# powerboard.net
KiCad netlist of a schematic drawn in EAGLE
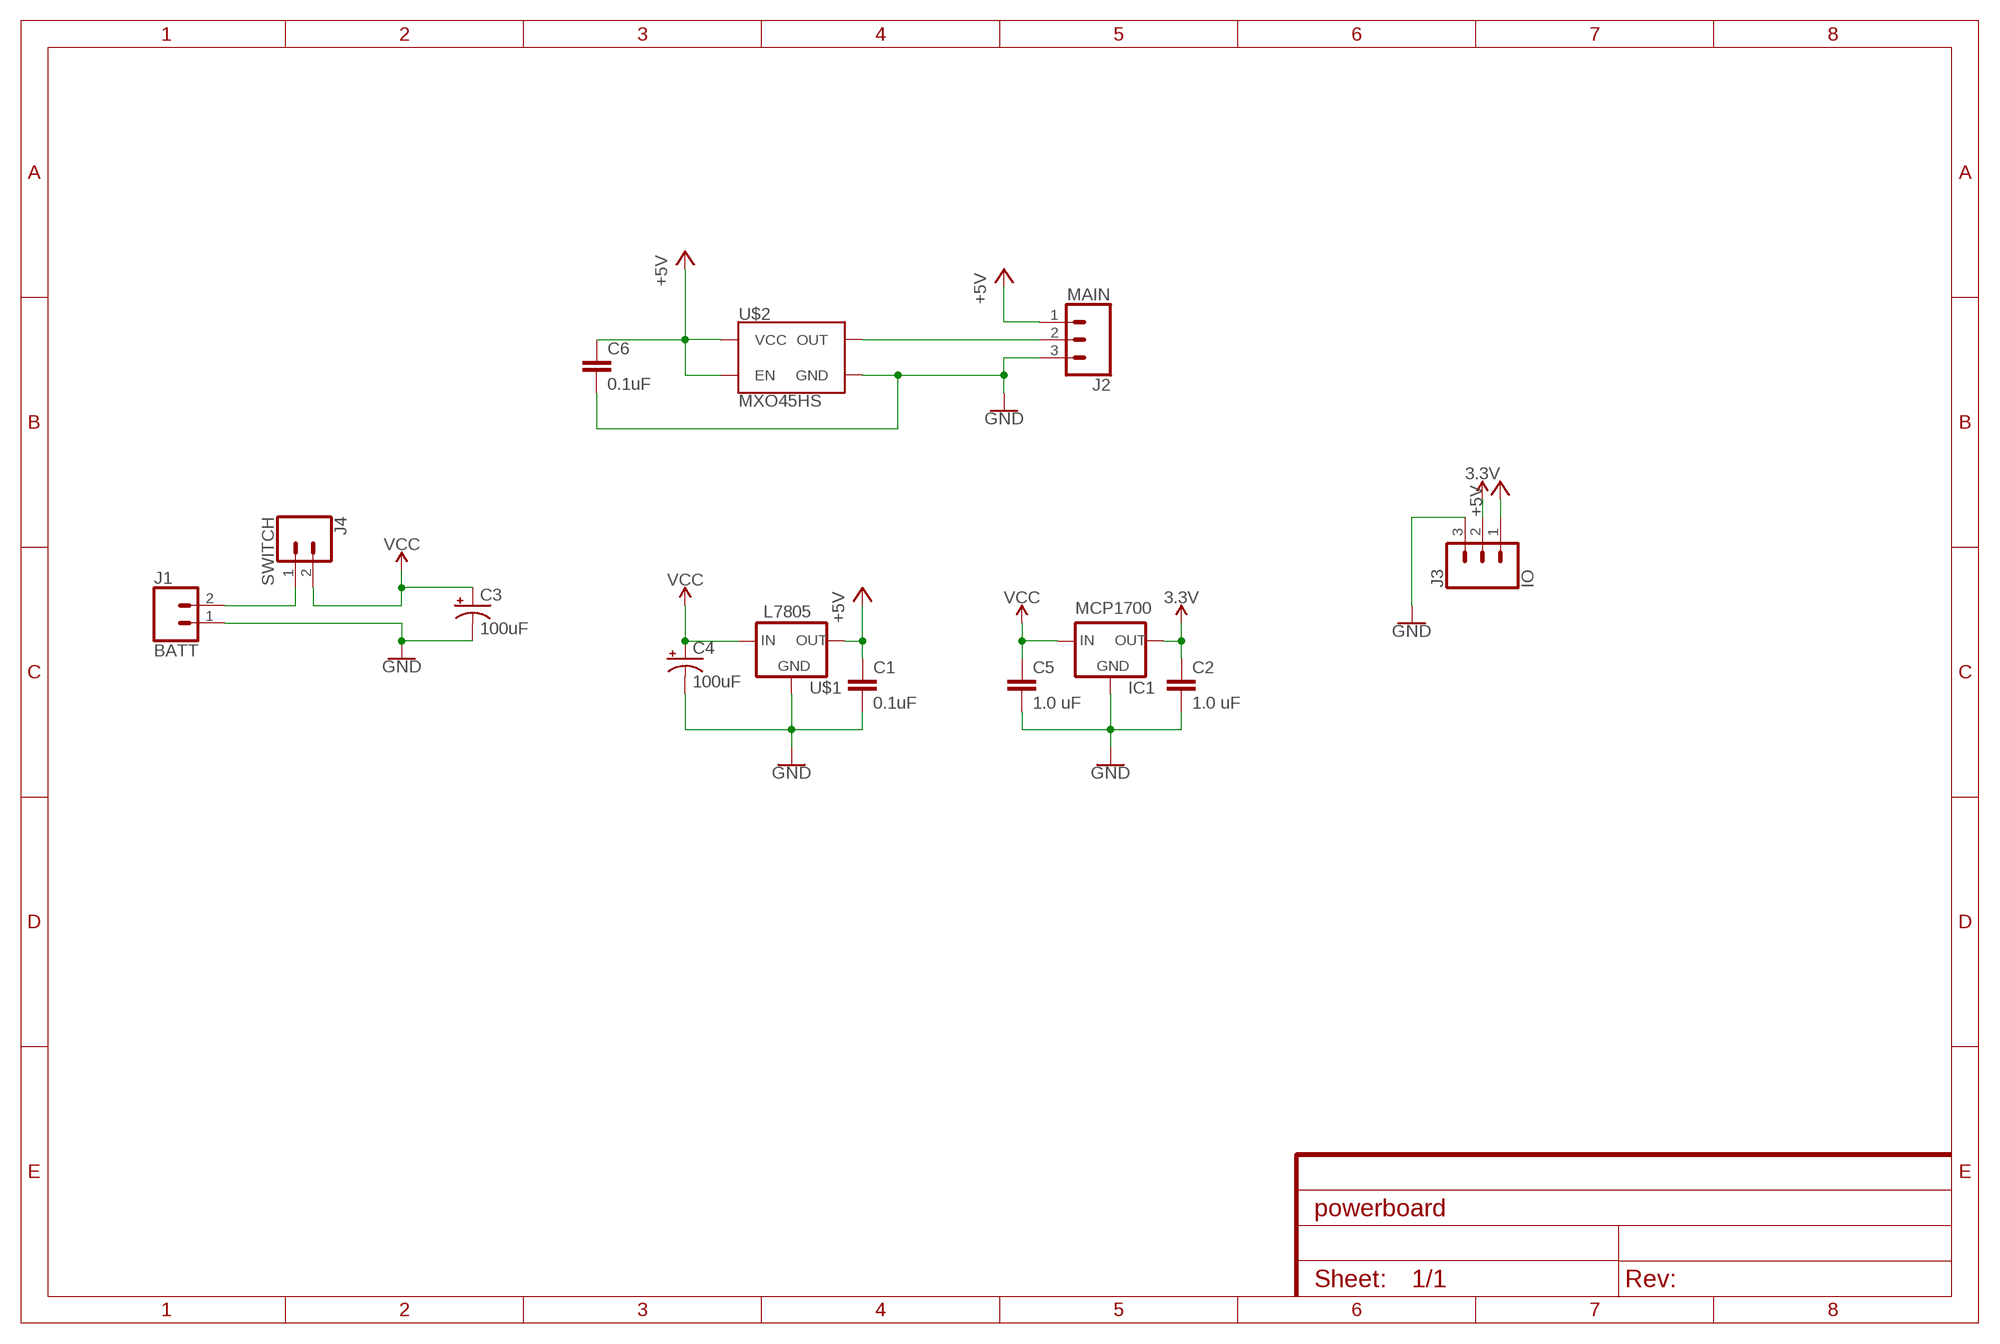
[diagram p0: schematic, sheet 1]

(export (version "E")
  (design (tool "Eeschema 10.0.6"))
  (components
    (comp (ref "C1")
      (value "0.1uF")
      (footprint "eagle-import:C2.5-3")
      (libsource (lib "eagle-import") (part "C2,5-3"))
    )
    (comp (ref "C2")
      (value "1.0 uF")
      (footprint "eagle-import:C2.5-3")
      (libsource (lib "eagle-import") (part "C2,5-3"))
    )
    (comp (ref "C3")
      (value "100uF")
      (footprint "eagle-import:CPOL-RADIAL-2.5MM-6.5MM")
      (libsource (lib "eagle-import") (part "100UF-POLAR-RADIAL-2.5MM-25V-20%"))
    )
    (comp (ref "C4")
      (value "100uF")
      (footprint "eagle-import:CPOL-RADIAL-2.5MM-6.5MM")
      (libsource (lib "eagle-import") (part "100UF-POLAR-RADIAL-2.5MM-25V-20%"))
    )
    (comp (ref "C5")
      (value "1.0 uF")
      (footprint "eagle-import:C2.5-3")
      (libsource (lib "eagle-import") (part "C2,5-3"))
    )
    (comp (ref "C6")
      (value "0.1uF")
      (footprint "eagle-import:C2.5-3")
      (libsource (lib "eagle-import") (part "C2,5-3"))
    )
    (comp (ref "IC1")
      (value "MCP1700")
      (footprint "eagle-import:TO-92-AMMO")
      (libsource (lib "eagle-import") (part "MCP1700"))
    )
    (comp (ref "J1")
      (value "BATT")
      (footprint "eagle-import:SCREWTERMINAL-5MM-2")
      (libsource (lib "eagle-import") (part "CONN_025MM"))
    )
    (comp (ref "J2")
      (value "MAIN")
      (footprint "eagle-import:SCREWTERMINAL-5MM-3")
      (libsource (lib "eagle-import") (part "CONN_03-SCREW-5MM"))
    )
    (comp (ref "J3")
      (value "IO")
      (footprint "eagle-import:SCREWTERMINAL-5MM-3")
      (libsource (lib "eagle-import") (part "CONN_03-SCREW-5MM"))
    )
    (comp (ref "J4")
      (value "SWITCH")
      (footprint "eagle-import:1X02")
      (libsource (lib "eagle-import") (part "CONN_02"))
    )
    (comp (ref "U$1")
      (value "L7805")
      (footprint "eagle-import:TO-220-FLAT")
      (libsource (lib "eagle-import") (part "VREG_IGOTO-220"))
    )
    (comp (ref "U$2")
      (value "MXO45HS")
      (footprint "eagle-import:DIL08-HALF")
      (libsource (lib "eagle-import") (part "MXO45HS"))
    )
  )
  (nets
    (net (code "1") (name "+5V") (class "Default")
      (node (ref "C1") (pin "1") (pinfunction "1_1") (pintype "passive"))
      (node (ref "C6") (pin "1") (pinfunction "1_1") (pintype "passive"))
      (node (ref "J2") (pin "1") (pinfunction "1_1") (pintype "passive"))
      (node (ref "J3") (pin "1") (pinfunction "1_1") (pintype "passive"))
      (node (ref "U$1") (pin "OUT") (pinfunction "OUT_OUT") (pintype "output"))
      (node (ref "U$2") (pin "1") (pinfunction "EN_1") (pintype "bidirectional"))
      (node (ref "U$2") (pin "8") (pinfunction "VCC_8") (pintype "bidirectional"))
    )
    (net (code "2") (name "3.3V") (class "Default")
      (node (ref "C2") (pin "1") (pinfunction "1_1") (pintype "passive"))
      (node (ref "IC1") (pin "3") (pinfunction "OUT_3") (pintype "output"))
      (node (ref "J3") (pin "2") (pinfunction "2_2") (pintype "passive"))
    )
    (net (code "3") (name "GND") (class "Default")
      (node (ref "C1") (pin "2") (pinfunction "2_2") (pintype "passive"))
      (node (ref "C2") (pin "2") (pinfunction "2_2") (pintype "passive"))
      (node (ref "C3") (pin "2") (pinfunction "-_2") (pintype "passive"))
      (node (ref "C4") (pin "2") (pinfunction "-_2") (pintype "passive"))
      (node (ref "C5") (pin "2") (pinfunction "2_2") (pintype "passive"))
      (node (ref "C6") (pin "2") (pinfunction "2_2") (pintype "passive"))
      (node (ref "IC1") (pin "1") (pinfunction "GND_1") (pintype "input"))
      (node (ref "J1") (pin "1") (pinfunction "1_1") (pintype "passive"))
      (node (ref "J2") (pin "3") (pinfunction "3_3") (pintype "passive"))
      (node (ref "J3") (pin "3") (pinfunction "3_3") (pintype "passive"))
      (node (ref "U$1") (pin "GND") (pinfunction "GND_GND") (pintype "input"))
      (node (ref "U$2") (pin "4") (pinfunction "GND_4") (pintype "bidirectional"))
    )
    (net (code "4") (name "Net-(J1-Pad2)") (class "Default")
      (node (ref "J1") (pin "2") (pinfunction "2_2") (pintype "passive"))
      (node (ref "J4") (pin "1") (pinfunction "1_1") (pintype "passive"))
    )
    (net (code "5") (name "Net-(U$2-OUT)") (class "Default")
      (node (ref "J2") (pin "2") (pinfunction "2_2") (pintype "passive"))
      (node (ref "U$2") (pin "5") (pinfunction "OUT_5") (pintype "bidirectional"))
    )
    (net (code "6") (name "VCC") (class "Default")
      (node (ref "C3") (pin "1") (pinfunction "+_1") (pintype "passive"))
      (node (ref "C4") (pin "1") (pinfunction "+_1") (pintype "passive"))
      (node (ref "C5") (pin "1") (pinfunction "1_1") (pintype "passive"))
      (node (ref "IC1") (pin "2") (pinfunction "IN_2") (pintype "input"))
      (node (ref "J4") (pin "2") (pinfunction "2_2") (pintype "passive"))
      (node (ref "U$1") (pin "IN") (pinfunction "IN_IN") (pintype "input"))
    )
  )
)
